# Regulators.net
KiCad netlist of a schematic drawn in Altium Designer
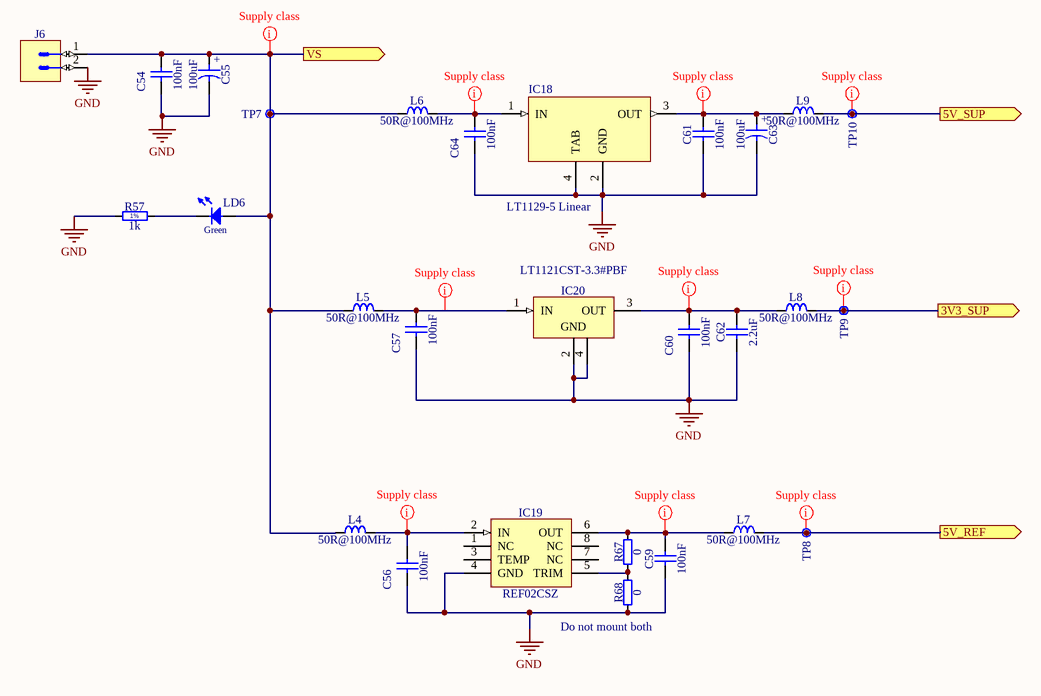
[diagram p0: Regulators.SchDoc]

(export (version "E")
  (design (tool "Eeschema 10.0.6"))
  (components
    (comp (ref "C54")
      (value "100nF")
      (footprint "CAPC2012X135N")
      (description "Non-polarised capacitor")
      (fields
        (field (name "PART NUMBER") "CC0805_100NF_50V_10%_X7R")
        (field (name "VOLTAGE") "50V")
        (field (name "AUTHOR") "CERN DEM JLC")
      )
      (libsource (lib "Capacitors") (part "Capacitor - non polarized"))
    )
    (comp (ref "C55")
      (value "100uF")
      (footprint "CAPAE660X540N")
      (description "Polarised capacitor")
      (fields
        (field (name "PART NUMBER") "CAE660-540_100UF_16V_20%")
        (field (name "VOLTAGE") "16V")
        (field (name "AUTHOR") "CERN DEM JLC")
      )
      (libsource (lib "Capacitors") (part "Capacitor - polarized"))
    )
    (comp (ref "C56")
      (value "100nF")
      (footprint "CAPC2012X135N")
      (description "Non-polarised capacitor")
      (fields
        (field (name "PART NUMBER") "CC0805_100NF_50V_10%_X7R")
        (field (name "VOLTAGE") "50V")
        (field (name "AUTHOR") "CERN DEM JLC")
      )
      (libsource (lib "Capacitors") (part "Capacitor - non polarized"))
    )
    (comp (ref "C57")
      (value "100nF")
      (footprint "CAPC2012X135N")
      (description "Non-polarised capacitor")
      (fields
        (field (name "PART NUMBER") "CC0805_100NF_50V_10%_X7R")
        (field (name "VOLTAGE") "50V")
        (field (name "AUTHOR") "CERN DEM JLC")
      )
      (libsource (lib "Capacitors") (part "Capacitor - non polarized"))
    )
    (comp (ref "C59")
      (value "100nF")
      (footprint "CAPC2012X135N")
      (description "Non-polarised capacitor")
      (fields
        (field (name "PART NUMBER") "CC0805_100NF_50V_10%_X7R")
        (field (name "VOLTAGE") "50V")
        (field (name "AUTHOR") "CERN DEM JLC")
      )
      (libsource (lib "Capacitors") (part "Capacitor - non polarized"))
    )
    (comp (ref "C60")
      (value "100nF")
      (footprint "CAPC2012X135N")
      (description "Non-polarised capacitor")
      (fields
        (field (name "PART NUMBER") "CC0805_100NF_50V_10%_X7R")
        (field (name "VOLTAGE") "50V")
        (field (name "AUTHOR") "CERN DEM JLC")
      )
      (libsource (lib "Capacitors") (part "Capacitor - non polarized"))
    )
    (comp (ref "C61")
      (value "100nF")
      (footprint "CAPC2012X135N")
      (description "Non-polarised capacitor")
      (fields
        (field (name "PART NUMBER") "CC0805_100NF_50V_10%_X7R")
        (field (name "VOLTAGE") "50V")
        (field (name "AUTHOR") "CERN DEM JLC")
      )
      (libsource (lib "Capacitors") (part "Capacitor - non polarized"))
    )
    (comp (ref "C62")
      (value "2.2uF")
      (footprint "CAPC2012X135N")
      (description "Non-polarised capacitor")
      (fields
        (field (name "PART NUMBER") "CC0805_2.2UF_16V_10%_X7R")
        (field (name "VOLTAGE") "16V")
        (field (name "AUTHOR") "CERN DEM JLC")
      )
      (libsource (lib "Capacitors") (part "Capacitor - non polarized"))
    )
    (comp (ref "C63")
      (value "100uF")
      (footprint "CAPAE660X540N")
      (description "Polarised capacitor")
      (fields
        (field (name "PART NUMBER") "CAE660-540_100UF_16V_20%")
        (field (name "VOLTAGE") "16V")
        (field (name "AUTHOR") "CERN DEM JLC")
      )
      (libsource (lib "Capacitors") (part "Capacitor - polarized"))
    )
    (comp (ref "C64")
      (value "100nF")
      (footprint "CAPC2012X135N")
      (description "Non-polarised capacitor")
      (fields
        (field (name "PART NUMBER") "CC0805_100NF_50V_10%_X7R")
        (field (name "VOLTAGE") "50V")
        (field (name "AUTHOR") "CERN DEM JLC")
      )
      (libsource (lib "Capacitors") (part "Capacitor - non polarized"))
    )
    (comp (ref "IC18")
      (value "LT1129-5 Linear")
      (footprint "SOT230P700X175-4N")
      (fields (field (name "MANUFACTURER") "Linear"))
      (libsource (lib "Additional") (part "LT1129-5"))
    )
    (comp (ref "IC19")
      (value "REF02CSZ")
      (footprint "SOIC127P600X175-8N")
      (description "Precision Voltage Reference/Temperature Transducer")
      (fields (field (name "MANUFACTURER") "ANALOG DEVICES") (field (name "AUTHOR") "CERN DEM JLC"))
      (libsource (lib "ICs And Semiconductors") (part "REF02CSZ"))
    )
    (comp (ref "IC20")
      (value "LT1121CST-3.3#PBF")
      (footprint "SOT230P700X180-4N")
      (description "3-Terminal Regulator 1=IN 2=GND 3=OUT 4=GND")
      (fields (field (name "MANUFACTURER") "LINEAR TECHNOLOGY") (field (name "AUTHOR") "CERN DEM JLC"))
      (libsource (lib "ICs And Semiconductors") (part "REG3+1 1IN-2GND-3OUT+4GND"))
    )
    (comp (ref "J6")
      (value "MATE-N-LOK")
      (footprint "TYCO_350786-1")
      (description "Connector 2 Male")
      (fields
        (field (name "PART NUMBER") "TYCO_350786-1")
        (field (name "MANUFACTURER") "TYCO ELECTRONICS")
        (field (name "AUTHOR") "CERN DEM JMW")
      )
      (libsource (lib "Connectors") (part "Connector 2 Male"))
    )
    (comp (ref "L4")
      (value "50R@100MHz")
      (footprint "IND_MURATA_BLM31PG")
      (description "Inductor")
      (fields
        (field (name "PART NUMBER") "IND1206_MURATA_BLM31PG500SN1")
        (field (name "POWER") "3.5A")
        (field (name "AUTHOR") "CERN DEM JLC")
      )
      (libsource (lib "Inductors & Transformers") (part "Inductor"))
    )
    (comp (ref "L5")
      (value "50R@100MHz")
      (footprint "IND_MURATA_BLM31PG")
      (description "Inductor")
      (fields
        (field (name "PART NUMBER") "IND1206_MURATA_BLM31PG500SN1")
        (field (name "POWER") "3.5A")
        (field (name "AUTHOR") "CERN DEM JLC")
      )
      (libsource (lib "Inductors & Transformers") (part "Inductor"))
    )
    (comp (ref "L6")
      (value "50R@100MHz")
      (footprint "IND_MURATA_BLM31PG")
      (description "Inductor")
      (fields
        (field (name "PART NUMBER") "IND1206_MURATA_BLM31PG500SN1")
        (field (name "POWER") "3.5A")
        (field (name "AUTHOR") "CERN DEM JLC")
      )
      (libsource (lib "Inductors & Transformers") (part "Inductor"))
    )
    (comp (ref "L7")
      (value "50R@100MHz")
      (footprint "IND_MURATA_BLM31PG")
      (description "Inductor")
      (fields
        (field (name "PART NUMBER") "IND1206_MURATA_BLM31PG500SN1")
        (field (name "POWER") "3.5A")
        (field (name "AUTHOR") "CERN DEM JLC")
      )
      (libsource (lib "Inductors & Transformers") (part "Inductor"))
    )
    (comp (ref "L8")
      (value "50R@100MHz")
      (footprint "IND_MURATA_BLM31PG")
      (description "Inductor")
      (fields
        (field (name "PART NUMBER") "IND1206_MURATA_BLM31PG500SN1")
        (field (name "POWER") "3.5A")
        (field (name "AUTHOR") "CERN DEM JLC")
      )
      (libsource (lib "Inductors & Transformers") (part "Inductor"))
    )
    (comp (ref "L9")
      (value "50R@100MHz")
      (footprint "IND_MURATA_BLM31PG")
      (description "Inductor")
      (fields
        (field (name "PART NUMBER") "IND1206_MURATA_BLM31PG500SN1")
        (field (name "POWER") "3.5A")
        (field (name "AUTHOR") "CERN DEM JLC")
      )
      (libsource (lib "Inductors & Transformers") (part "Inductor"))
    )
    (comp (ref "LD6")
      (value "Green")
      (footprint "LED_OSRAM_LGR971")
      (description "LED Green 1C 2A")
      (fields
        (field (name "PART NUMBER") "LED_OSRAM_LGR971")
        (field (name "MANUFACTURER") "OSRAM")
        (field (name "AUTHOR") "CERN DEM JLC")
      )
      (libsource (lib "ICs And Semiconductors") (part "LED Green 1C 2A"))
    )
    (comp (ref "R57")
      (value "1k")
      (footprint "RESC2012X60N")
      (description "Resistor - 1%")
      (fields
        (field (name "PART NUMBER") "R0805_1K_1%_0.125W_100PPM")
        (field (name "POWER") "0.125W")
        (field (name "AUTHOR") "CERN DEM JLC")
      )
      (libsource (lib "Resistors") (part "Resistor - 1%"))
    )
    (comp (ref "R67")
      (value "0")
      (footprint "RESC2012X60N")
      (description "Resistor")
      (fields
        (field (name "PART NUMBER") "R0805_0R_JUMPER")
        (field (name "MANUFACTURER") "GENERIC")
        (field (name "AUTHOR") "CERN DEM JLC")
      )
      (libsource (lib "Resistors") (part "Resistor"))
    )
    (comp (ref "R68")
      (value "0")
      (footprint "RESC2012X60N")
      (description "Resistor")
      (fields
        (field (name "PART NUMBER") "R0805_0R_JUMPER")
        (field (name "MANUFACTURER") "GENERIC")
        (field (name "AUTHOR") "CERN DEM JLC")
      )
      (libsource (lib "Resistors") (part "Resistor"))
    )
    (comp (ref "TP7")
      (value "Test Point")
      (footprint "VERO_20-2136")
      (fields
        (field (name "PART NUMBER") "VERO_20-2136")
        (field (name "MANUFACTURER") "VERO TECHNOLOGIES")
        (field (name "MANUFACTURER PART NUMBER") "20-2136")
        (field (name "AUTHOR") "CERN DEM JLC")
      )
      (libsource (lib "Connectors") (part "Test Point"))
    )
    (comp (ref "TP8")
      (value "Test Point")
      (footprint "VERO_20-2136")
      (fields
        (field (name "PART NUMBER") "VERO_20-2136")
        (field (name "MANUFACTURER") "VERO TECHNOLOGIES")
        (field (name "MANUFACTURER PART NUMBER") "20-2136")
        (field (name "AUTHOR") "CERN DEM JLC")
      )
      (libsource (lib "Connectors") (part "Test Point"))
    )
    (comp (ref "TP9")
      (value "Test Point")
      (footprint "VERO_20-2136")
      (fields
        (field (name "PART NUMBER") "VERO_20-2136")
        (field (name "MANUFACTURER") "VERO TECHNOLOGIES")
        (field (name "MANUFACTURER PART NUMBER") "20-2136")
        (field (name "AUTHOR") "CERN DEM JLC")
      )
      (libsource (lib "Connectors") (part "Test Point"))
    )
    (comp (ref "TP10")
      (value "Test Point")
      (footprint "VERO_20-2136")
      (fields
        (field (name "PART NUMBER") "VERO_20-2136")
        (field (name "MANUFACTURER") "VERO TECHNOLOGIES")
        (field (name "MANUFACTURER PART NUMBER") "20-2136")
        (field (name "AUTHOR") "CERN DEM JLC")
      )
      (libsource (lib "Connectors") (part "Test Point"))
    )
  )
  (nets
    (net (code "1") (name "/3V3_SUP") (class "Default")
      (node (ref "L8") (pin "2") (pinfunction "2_2") (pintype "passive"))
      (node (ref "TP9") (pin "1") (pinfunction "1_1") (pintype "bidirectional"))
    )
    (net (code "2") (name "/5V_REF") (class "Default")
      (node (ref "L7") (pin "2") (pinfunction "2_2") (pintype "passive"))
      (node (ref "TP8") (pin "1") (pinfunction "1_1") (pintype "bidirectional"))
    )
    (net (code "3") (name "/5V_SUP") (class "Default")
      (node (ref "L9") (pin "2") (pinfunction "2_2") (pintype "passive"))
      (node (ref "TP10") (pin "1") (pinfunction "1_1") (pintype "bidirectional"))
    )
    (net (code "4") (name "/VS") (class "Default")
      (node (ref "C54") (pin "2") (pinfunction "2_2") (pintype "passive"))
      (node (ref "C55") (pin "1") (pinfunction "1_1") (pintype "passive"))
      (node (ref "J6") (pin "1") (pinfunction "1_1") (pintype "bidirectional"))
      (node (ref "L4") (pin "1") (pinfunction "1_1") (pintype "passive"))
      (node (ref "L5") (pin "1") (pinfunction "1_1") (pintype "passive"))
      (node (ref "L6") (pin "1") (pinfunction "1_1") (pintype "passive"))
      (node (ref "LD6") (pin "2") (pinfunction "A_2") (pintype "passive"))
      (node (ref "TP7") (pin "1") (pinfunction "1_1") (pintype "bidirectional"))
    )
    (net (code "5") (name "GND") (class "Default")
      (node (ref "C54") (pin "1") (pinfunction "1_1") (pintype "passive"))
      (node (ref "C55") (pin "2") (pinfunction "2_2") (pintype "passive"))
      (node (ref "C56") (pin "1") (pinfunction "1_1") (pintype "passive"))
      (node (ref "C57") (pin "1") (pinfunction "1_1") (pintype "passive"))
      (node (ref "C59") (pin "1") (pinfunction "1_1") (pintype "passive"))
      (node (ref "C60") (pin "1") (pinfunction "1_1") (pintype "passive"))
      (node (ref "C61") (pin "1") (pinfunction "1_1") (pintype "passive"))
      (node (ref "C62") (pin "1") (pinfunction "1_1") (pintype "passive"))
      (node (ref "C63") (pin "2") (pinfunction "2_2") (pintype "passive"))
      (node (ref "C64") (pin "1") (pinfunction "1_1") (pintype "passive"))
      (node (ref "IC18") (pin "2") (pinfunction "GND_2") (pintype "power_in"))
      (node (ref "IC18") (pin "4") (pinfunction "TAB_4") (pintype "power_in"))
      (node (ref "IC19") (pin "4") (pinfunction "GND_4") (pintype "power_in"))
      (node (ref "IC20") (pin "2") (pinfunction "GND_2") (pintype "power_in"))
      (node (ref "IC20") (pin "4") (pinfunction "GND_4") (pintype "power_in"))
      (node (ref "J6") (pin "2") (pinfunction "2_2") (pintype "bidirectional"))
      (node (ref "R57") (pin "1") (pinfunction "1_1") (pintype "passive"))
      (node (ref "R68") (pin "1") (pinfunction "1_1") (pintype "passive"))
    )
    (net (code "6") (name "Net-(IC18-IN)") (class "Default")
      (node (ref "C64") (pin "2") (pinfunction "2_2") (pintype "passive"))
      (node (ref "IC18") (pin "1") (pinfunction "IN_1") (pintype "input"))
      (node (ref "L6") (pin "2") (pinfunction "2_2") (pintype "passive"))
    )
    (net (code "7") (name "Net-(IC18-OUT)") (class "Default")
      (node (ref "C61") (pin "2") (pinfunction "2_2") (pintype "passive"))
      (node (ref "C63") (pin "1") (pinfunction "1_1") (pintype "passive"))
      (node (ref "IC18") (pin "3") (pinfunction "OUT_3") (pintype "output"))
      (node (ref "L9") (pin "1") (pinfunction "1_1") (pintype "passive"))
    )
    (net (code "8") (name "Net-(IC19-IN)") (class "Default")
      (node (ref "C56") (pin "2") (pinfunction "2_2") (pintype "passive"))
      (node (ref "IC19") (pin "2") (pinfunction "IN_2") (pintype "input"))
      (node (ref "L4") (pin "2") (pinfunction "2_2") (pintype "passive"))
    )
    (net (code "9") (name "Net-(IC19-OUT)") (class "Default")
      (node (ref "C59") (pin "2") (pinfunction "2_2") (pintype "passive"))
      (node (ref "IC19") (pin "6") (pinfunction "OUT_6") (pintype "power_in"))
      (node (ref "L7") (pin "1") (pinfunction "1_1") (pintype "passive"))
      (node (ref "R67") (pin "2") (pinfunction "2_2") (pintype "passive"))
    )
    (net (code "10") (name "Net-(IC19-TRIM)") (class "Default")
      (node (ref "IC19") (pin "5") (pinfunction "TRIM_5") (pintype "passive"))
      (node (ref "R67") (pin "1") (pinfunction "1_1") (pintype "passive"))
      (node (ref "R68") (pin "2") (pinfunction "2_2") (pintype "passive"))
    )
    (net (code "11") (name "Net-(IC20-IN)") (class "Default")
      (node (ref "C57") (pin "2") (pinfunction "2_2") (pintype "passive"))
      (node (ref "IC20") (pin "1") (pinfunction "IN_1") (pintype "input"))
      (node (ref "L5") (pin "2") (pinfunction "2_2") (pintype "passive"))
    )
    (net (code "12") (name "Net-(IC20-OUT)") (class "Default")
      (node (ref "C60") (pin "2") (pinfunction "2_2") (pintype "passive"))
      (node (ref "C62") (pin "2") (pinfunction "2_2") (pintype "passive"))
      (node (ref "IC20") (pin "3") (pinfunction "OUT_3") (pintype "power_in"))
      (node (ref "L8") (pin "1") (pinfunction "1_1") (pintype "passive"))
    )
    (net (code "13") (name "Net-(LD6-C)") (class "Default")
      (node (ref "LD6") (pin "1") (pinfunction "C_1") (pintype "passive"))
      (node (ref "R57") (pin "2") (pinfunction "2_2") (pintype "passive"))
    )
    (net (code "14") (name "unconnected-(IC19-NC-Pad1)") (class "Default")
      (node (ref "IC19") (pin "1") (pinfunction "NC_1") (pintype "passive"))
    )
    (net (code "15") (name "unconnected-(IC19-NC-Pad7)") (class "Default")
      (node (ref "IC19") (pin "7") (pinfunction "NC_7") (pintype "passive"))
    )
    (net (code "16") (name "unconnected-(IC19-NC-Pad8)") (class "Default")
      (node (ref "IC19") (pin "8") (pinfunction "NC_8") (pintype "passive"))
    )
    (net (code "17") (name "unconnected-(IC19-TEMP-Pad3)") (class "Default")
      (node (ref "IC19") (pin "3") (pinfunction "TEMP_3") (pintype "passive"))
    )
  )
)
